# bumper.net
KiCad netlist of a schematic drawn in EAGLE
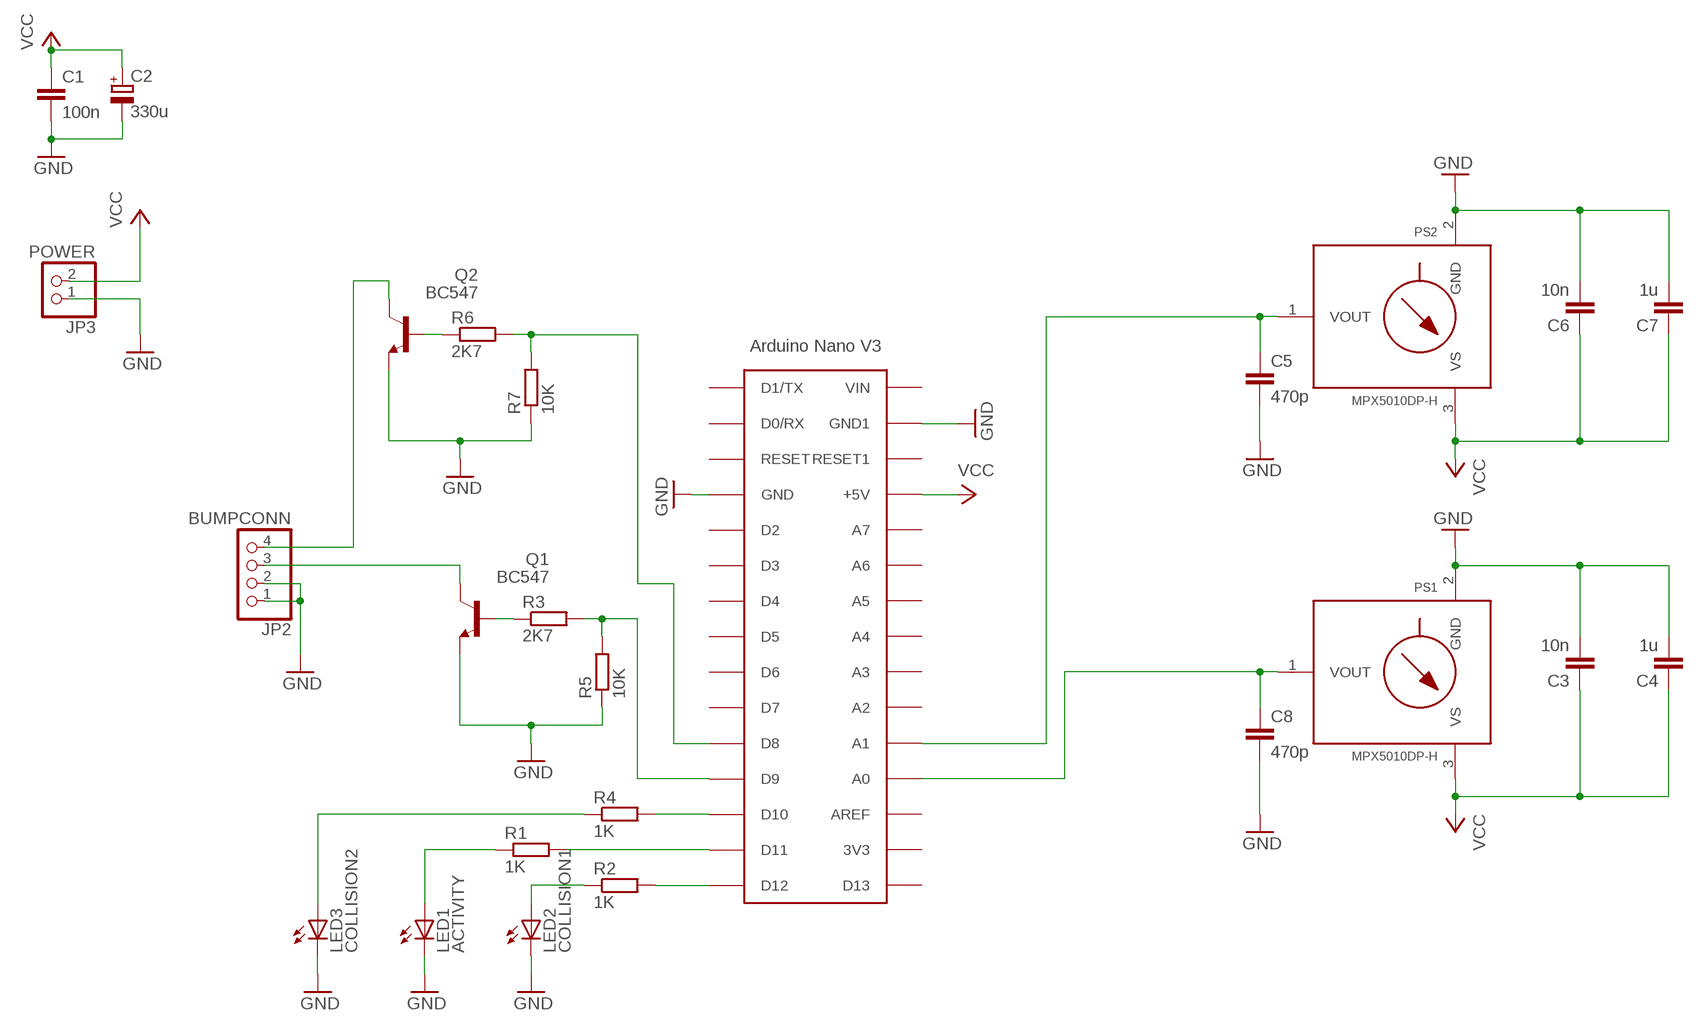
[diagram p0: schematic, sheet 1]

(export (version "E")
  (design (tool "Eeschema 10.0.6"))
  (components
    (comp (ref "C1")
      (value "100n")
      (footprint "eagle-import:C050-024X044")
      (libsource (lib "eagle-import") (part "C-EU050-024X044"))
    )
    (comp (ref "C2")
      (value "330u")
      (footprint "eagle-import:E2,5-6E")
      (libsource (lib "eagle-import") (part "CPOL-EUE2,5-6E"))
    )
    (comp (ref "C3")
      (value "10n")
      (footprint "eagle-import:C050-024X044")
      (libsource (lib "eagle-import") (part "C-EU050-024X044"))
    )
    (comp (ref "C4")
      (value "1u")
      (footprint "eagle-import:C050-035X075")
      (libsource (lib "eagle-import") (part "C-EU050-035X075"))
    )
    (comp (ref "C5")
      (value "470p")
      (footprint "eagle-import:C050-024X044")
      (libsource (lib "eagle-import") (part "C-EU050-024X044"))
    )
    (comp (ref "C6")
      (value "10n")
      (footprint "eagle-import:C050-024X044")
      (libsource (lib "eagle-import") (part "C-EU050-024X044"))
    )
    (comp (ref "C7")
      (value "1u")
      (footprint "eagle-import:C050-035X075")
      (libsource (lib "eagle-import") (part "C-EU050-035X075"))
    )
    (comp (ref "C8")
      (value "470p")
      (footprint "eagle-import:C050-024X044")
      (libsource (lib "eagle-import") (part "C-EU050-024X044"))
    )
    (comp (ref "JP2")
      (value "BUMPCONN")
      (footprint "eagle-import:1X04")
      (libsource (lib "eagle-import") (part "PINHD-1X4"))
    )
    (comp (ref "JP3")
      (value "POWER")
      (footprint "eagle-import:1X02")
      (libsource (lib "eagle-import") (part "PINHD-1X2"))
    )
    (comp (ref "LED1")
      (value "ACTIVITY")
      (footprint "eagle-import:LED5MM")
      (libsource (lib "eagle-import") (part "LED5MM"))
    )
    (comp (ref "LED2")
      (value "COLLISION1")
      (footprint "eagle-import:LED5MM")
      (libsource (lib "eagle-import") (part "LED5MM"))
    )
    (comp (ref "LED3")
      (value "COLLISION2")
      (footprint "eagle-import:LED5MM")
      (libsource (lib "eagle-import") (part "LED5MM"))
    )
    (comp (ref "PS1")
      (value "MPX5010DP-H")
      (footprint "eagle-import:867C-H")
      (libsource (lib "eagle-import") (part "MPX5010DP-H"))
    )
    (comp (ref "PS2")
      (value "MPX5010DP-H")
      (footprint "eagle-import:867C-H")
      (libsource (lib "eagle-import") (part "MPX5010DP-H"))
    )
    (comp (ref "Q1")
      (value "BC547")
      (footprint "eagle-import:TO92-EBC")
      (libsource (lib "eagle-import") (part "BC548"))
    )
    (comp (ref "Q2")
      (value "BC547")
      (footprint "eagle-import:TO92-EBC")
      (libsource (lib "eagle-import") (part "BC548"))
    )
    (comp (ref "R1")
      (value "1K")
      (footprint "eagle-import:0204_7")
      (libsource (lib "eagle-import") (part "R-EU_0204/7"))
    )
    (comp (ref "R2")
      (value "1K")
      (footprint "eagle-import:0204_7")
      (libsource (lib "eagle-import") (part "R-EU_0204/7"))
    )
    (comp (ref "R3")
      (value "2K7")
      (footprint "eagle-import:0204_7")
      (libsource (lib "eagle-import") (part "R-EU_0204/7"))
    )
    (comp (ref "R4")
      (value "1K")
      (footprint "eagle-import:0204_7")
      (libsource (lib "eagle-import") (part "R-EU_0204/7"))
    )
    (comp (ref "R5")
      (value "10K")
      (footprint "eagle-import:0204_7")
      (libsource (lib "eagle-import") (part "R-EU_0204/7"))
    )
    (comp (ref "R6")
      (value "2K7")
      (footprint "eagle-import:0204_7")
      (libsource (lib "eagle-import") (part "R-EU_0204/7"))
    )
    (comp (ref "R7")
      (value "10K")
      (footprint "eagle-import:0204_7")
      (libsource (lib "eagle-import") (part "R-EU_0204/7"))
    )
    (comp (ref "U$1")
      (value "ARDUINONANO")
      (footprint "eagle-import:PDIP-32")
      (libsource (lib "eagle-import") (part "ARDUINONANO"))
    )
  )
  (nets
    (net (code "1") (name "GND") (class "Default")
      (node (ref "C1") (pin "2") (pinfunction "2_2") (pintype "passive"))
      (node (ref "C2") (pin "-") (pinfunction "-_-") (pintype "passive"))
      (node (ref "C3") (pin "2") (pinfunction "2_2") (pintype "passive"))
      (node (ref "C4") (pin "2") (pinfunction "2_2") (pintype "passive"))
      (node (ref "C5") (pin "2") (pinfunction "2_2") (pintype "passive"))
      (node (ref "C6") (pin "2") (pinfunction "2_2") (pintype "passive"))
      (node (ref "C7") (pin "2") (pinfunction "2_2") (pintype "passive"))
      (node (ref "C8") (pin "2") (pinfunction "2_2") (pintype "passive"))
      (node (ref "JP2") (pin "1") (pinfunction "1_1") (pintype "passive"))
      (node (ref "JP2") (pin "2") (pinfunction "2_2") (pintype "passive"))
      (node (ref "JP3") (pin "1") (pinfunction "1_1") (pintype "passive"))
      (node (ref "LED1") (pin "K") (pinfunction "C_K") (pintype "passive"))
      (node (ref "LED2") (pin "K") (pinfunction "C_K") (pintype "passive"))
      (node (ref "LED3") (pin "K") (pinfunction "C_K") (pintype "passive"))
      (node (ref "PS1") (pin "2") (pinfunction "GND_2") (pintype "power_in"))
      (node (ref "PS2") (pin "2") (pinfunction "GND_2") (pintype "power_in"))
      (node (ref "Q1") (pin "E") (pinfunction "E_E") (pintype "passive"))
      (node (ref "Q2") (pin "E") (pinfunction "E_E") (pintype "passive"))
      (node (ref "R5") (pin "1") (pinfunction "1_1") (pintype "passive"))
      (node (ref "R7") (pin "1") (pinfunction "1_1") (pintype "passive"))
      (node (ref "U$1") (pin "GND") (pinfunction "GND_GND") (pintype "bidirectional"))
      (node (ref "U$1") (pin "GND1") (pinfunction "GND1_GND1") (pintype "bidirectional"))
    )
    (net (code "2") (name "Net-(JP2-Pad3)") (class "Default")
      (node (ref "JP2") (pin "3") (pinfunction "3_3") (pintype "passive"))
      (node (ref "Q1") (pin "C") (pinfunction "C_C") (pintype "passive"))
    )
    (net (code "3") (name "Net-(JP2-Pad4)") (class "Default")
      (node (ref "JP2") (pin "4") (pinfunction "4_4") (pintype "passive"))
      (node (ref "Q2") (pin "C") (pinfunction "C_C") (pintype "passive"))
    )
    (net (code "4") (name "Net-(LED1-PadA)") (class "Default")
      (node (ref "LED1") (pin "A") (pinfunction "A_A") (pintype "passive"))
      (node (ref "R1") (pin "1") (pinfunction "1_1") (pintype "passive"))
    )
    (net (code "5") (name "Net-(LED2-PadA)") (class "Default")
      (node (ref "LED2") (pin "A") (pinfunction "A_A") (pintype "passive"))
      (node (ref "R2") (pin "1") (pinfunction "1_1") (pintype "passive"))
    )
    (net (code "6") (name "Net-(LED3-PadA)") (class "Default")
      (node (ref "LED3") (pin "A") (pinfunction "A_A") (pintype "passive"))
      (node (ref "R4") (pin "1") (pinfunction "1_1") (pintype "passive"))
    )
    (net (code "7") (name "Net-(PS1-VOUT)") (class "Default")
      (node (ref "C8") (pin "1") (pinfunction "1_1") (pintype "passive"))
      (node (ref "PS1") (pin "1") (pinfunction "VOUT_1") (pintype "output"))
      (node (ref "U$1") (pin "A7") (pinfunction "A0_A7") (pintype "bidirectional"))
    )
    (net (code "8") (name "Net-(PS2-VOUT)") (class "Default")
      (node (ref "C5") (pin "1") (pinfunction "1_1") (pintype "passive"))
      (node (ref "PS2") (pin "1") (pinfunction "VOUT_1") (pintype "output"))
      (node (ref "U$1") (pin "A6") (pinfunction "A1_A6") (pintype "bidirectional"))
    )
    (net (code "9") (name "Net-(Q1-PadB)") (class "Default")
      (node (ref "Q1") (pin "B") (pinfunction "B_B") (pintype "passive"))
      (node (ref "R3") (pin "1") (pinfunction "1_1") (pintype "passive"))
    )
    (net (code "10") (name "Net-(Q2-PadB)") (class "Default")
      (node (ref "Q2") (pin "B") (pinfunction "B_B") (pintype "passive"))
      (node (ref "R6") (pin "1") (pinfunction "1_1") (pintype "passive"))
    )
    (net (code "11") (name "Net-(R1-Pad2)") (class "Default")
      (node (ref "R1") (pin "2") (pinfunction "2_2") (pintype "passive"))
      (node (ref "U$1") (pin "D11") (pinfunction "D11_D11") (pintype "bidirectional"))
    )
    (net (code "12") (name "Net-(R2-Pad2)") (class "Default")
      (node (ref "R2") (pin "2") (pinfunction "2_2") (pintype "passive"))
      (node (ref "U$1") (pin "D12") (pinfunction "D12_D12") (pintype "bidirectional"))
    )
    (net (code "13") (name "Net-(R3-Pad2)") (class "Default")
      (node (ref "R3") (pin "2") (pinfunction "2_2") (pintype "passive"))
      (node (ref "R5") (pin "2") (pinfunction "2_2") (pintype "passive"))
      (node (ref "U$1") (pin "D9") (pinfunction "D9_D9") (pintype "bidirectional"))
    )
    (net (code "14") (name "Net-(R4-Pad2)") (class "Default")
      (node (ref "R4") (pin "2") (pinfunction "2_2") (pintype "passive"))
      (node (ref "U$1") (pin "D10") (pinfunction "D10_D10") (pintype "bidirectional"))
    )
    (net (code "15") (name "Net-(R6-Pad2)") (class "Default")
      (node (ref "R6") (pin "2") (pinfunction "2_2") (pintype "passive"))
      (node (ref "R7") (pin "2") (pinfunction "2_2") (pintype "passive"))
      (node (ref "U$1") (pin "D8") (pinfunction "D8_D8") (pintype "bidirectional"))
    )
    (net (code "16") (name "VCC") (class "Default")
      (node (ref "C1") (pin "1") (pinfunction "1_1") (pintype "passive"))
      (node (ref "C2") (pin "+") (pinfunction "+_+") (pintype "passive"))
      (node (ref "C3") (pin "1") (pinfunction "1_1") (pintype "passive"))
      (node (ref "C4") (pin "1") (pinfunction "1_1") (pintype "passive"))
      (node (ref "C6") (pin "1") (pinfunction "1_1") (pintype "passive"))
      (node (ref "C7") (pin "1") (pinfunction "1_1") (pintype "passive"))
      (node (ref "JP3") (pin "2") (pinfunction "2_2") (pintype "passive"))
      (node (ref "PS1") (pin "3") (pinfunction "VS_3") (pintype "power_in"))
      (node (ref "PS2") (pin "3") (pinfunction "VS_3") (pintype "power_in"))
      (node (ref "U$1") (pin "+5V") (pinfunction "+5V_+5V") (pintype "bidirectional"))
    )
    (net (code "17") (name "unconnected-(PS1-NC-Pad4)") (class "Default")
      (node (ref "PS1") (pin "4") (pinfunction "NC_4") (pintype "no_connect"))
    )
    (net (code "18") (name "unconnected-(PS1-NC-Pad5)") (class "Default")
      (node (ref "PS1") (pin "5") (pinfunction "NC_5") (pintype "no_connect"))
    )
    (net (code "19") (name "unconnected-(PS1-NC-Pad6)") (class "Default")
      (node (ref "PS1") (pin "6") (pinfunction "NC_6") (pintype "no_connect"))
    )
    (net (code "20") (name "unconnected-(PS2-NC-Pad4)") (class "Default")
      (node (ref "PS2") (pin "4") (pinfunction "NC_4") (pintype "no_connect"))
    )
    (net (code "21") (name "unconnected-(PS2-NC-Pad5)") (class "Default")
      (node (ref "PS2") (pin "5") (pinfunction "NC_5") (pintype "no_connect"))
    )
    (net (code "22") (name "unconnected-(PS2-NC-Pad6)") (class "Default")
      (node (ref "PS2") (pin "6") (pinfunction "NC_6") (pintype "no_connect"))
    )
    (net (code "23") (name "unconnected-(U$1-A2-PadA5)") (class "Default")
      (node (ref "U$1") (pin "A5") (pinfunction "A2_A5") (pintype "bidirectional"))
    )
    (net (code "24") (name "unconnected-(U$1-A3-PadA4)") (class "Default")
      (node (ref "U$1") (pin "A4") (pinfunction "A3_A4") (pintype "bidirectional"))
    )
    (net (code "25") (name "unconnected-(U$1-A4-PadA3)") (class "Default")
      (node (ref "U$1") (pin "A3") (pinfunction "A4_A3") (pintype "bidirectional"))
    )
    (net (code "26") (name "unconnected-(U$1-A5-PadA2)") (class "Default")
      (node (ref "U$1") (pin "A2") (pinfunction "A5_A2") (pintype "bidirectional"))
    )
    (net (code "27") (name "unconnected-(U$1-A6-PadA1)") (class "Default")
      (node (ref "U$1") (pin "A1") (pinfunction "A6_A1") (pintype "bidirectional"))
    )
    (net (code "28") (name "unconnected-(U$1-A7-PadA0)") (class "Default")
      (node (ref "U$1") (pin "A0") (pinfunction "A7_A0") (pintype "bidirectional"))
    )
    (net (code "29") (name "unconnected-(U$1-Pad3V3)") (class "Default")
      (node (ref "U$1") (pin "3V3") (pinfunction "3V3_3V3") (pintype "bidirectional"))
    )
    (net (code "30") (name "unconnected-(U$1-PadAREF)") (class "Default")
      (node (ref "U$1") (pin "AREF") (pinfunction "AREF_AREF") (pintype "bidirectional"))
    )
    (net (code "31") (name "unconnected-(U$1-PadD0{slash}RX)") (class "Default")
      (node (ref "U$1") (pin "D0/RX") (pinfunction "D0/RX_D0/RX") (pintype "bidirectional"))
    )
    (net (code "32") (name "unconnected-(U$1-PadD1{slash}TX)") (class "Default")
      (node (ref "U$1") (pin "D1/TX") (pinfunction "D1/TX_D1/TX") (pintype "bidirectional"))
    )
    (net (code "33") (name "unconnected-(U$1-PadD2)") (class "Default")
      (node (ref "U$1") (pin "D2") (pinfunction "D2_D2") (pintype "bidirectional"))
    )
    (net (code "34") (name "unconnected-(U$1-PadD3)") (class "Default")
      (node (ref "U$1") (pin "D3") (pinfunction "D3_D3") (pintype "bidirectional"))
    )
    (net (code "35") (name "unconnected-(U$1-PadD4)") (class "Default")
      (node (ref "U$1") (pin "D4") (pinfunction "D4_D4") (pintype "bidirectional"))
    )
    (net (code "36") (name "unconnected-(U$1-PadD5)") (class "Default")
      (node (ref "U$1") (pin "D5") (pinfunction "D5_D5") (pintype "bidirectional"))
    )
    (net (code "37") (name "unconnected-(U$1-PadD6)") (class "Default")
      (node (ref "U$1") (pin "D6") (pinfunction "D6_D6") (pintype "bidirectional"))
    )
    (net (code "38") (name "unconnected-(U$1-PadD7)") (class "Default")
      (node (ref "U$1") (pin "D7") (pinfunction "D7_D7") (pintype "bidirectional"))
    )
    (net (code "39") (name "unconnected-(U$1-PadD13)") (class "Default")
      (node (ref "U$1") (pin "D13") (pinfunction "D13_D13") (pintype "bidirectional"))
    )
    (net (code "40") (name "unconnected-(U$1-PadRESET)") (class "Default")
      (node (ref "U$1") (pin "RESET") (pinfunction "RESET_RESET") (pintype "bidirectional"))
    )
    (net (code "41") (name "unconnected-(U$1-PadRESET1)") (class "Default")
      (node (ref "U$1") (pin "RESET1") (pinfunction "RESET1_RESET1") (pintype "bidirectional"))
    )
    (net (code "42") (name "unconnected-(U$1-PadVIN)") (class "Default")
      (node (ref "U$1") (pin "VIN") (pinfunction "VIN_VIN") (pintype "bidirectional"))
    )
  )
)
